# IC2.net
KiCad netlist of a schematic drawn in Altium Designer
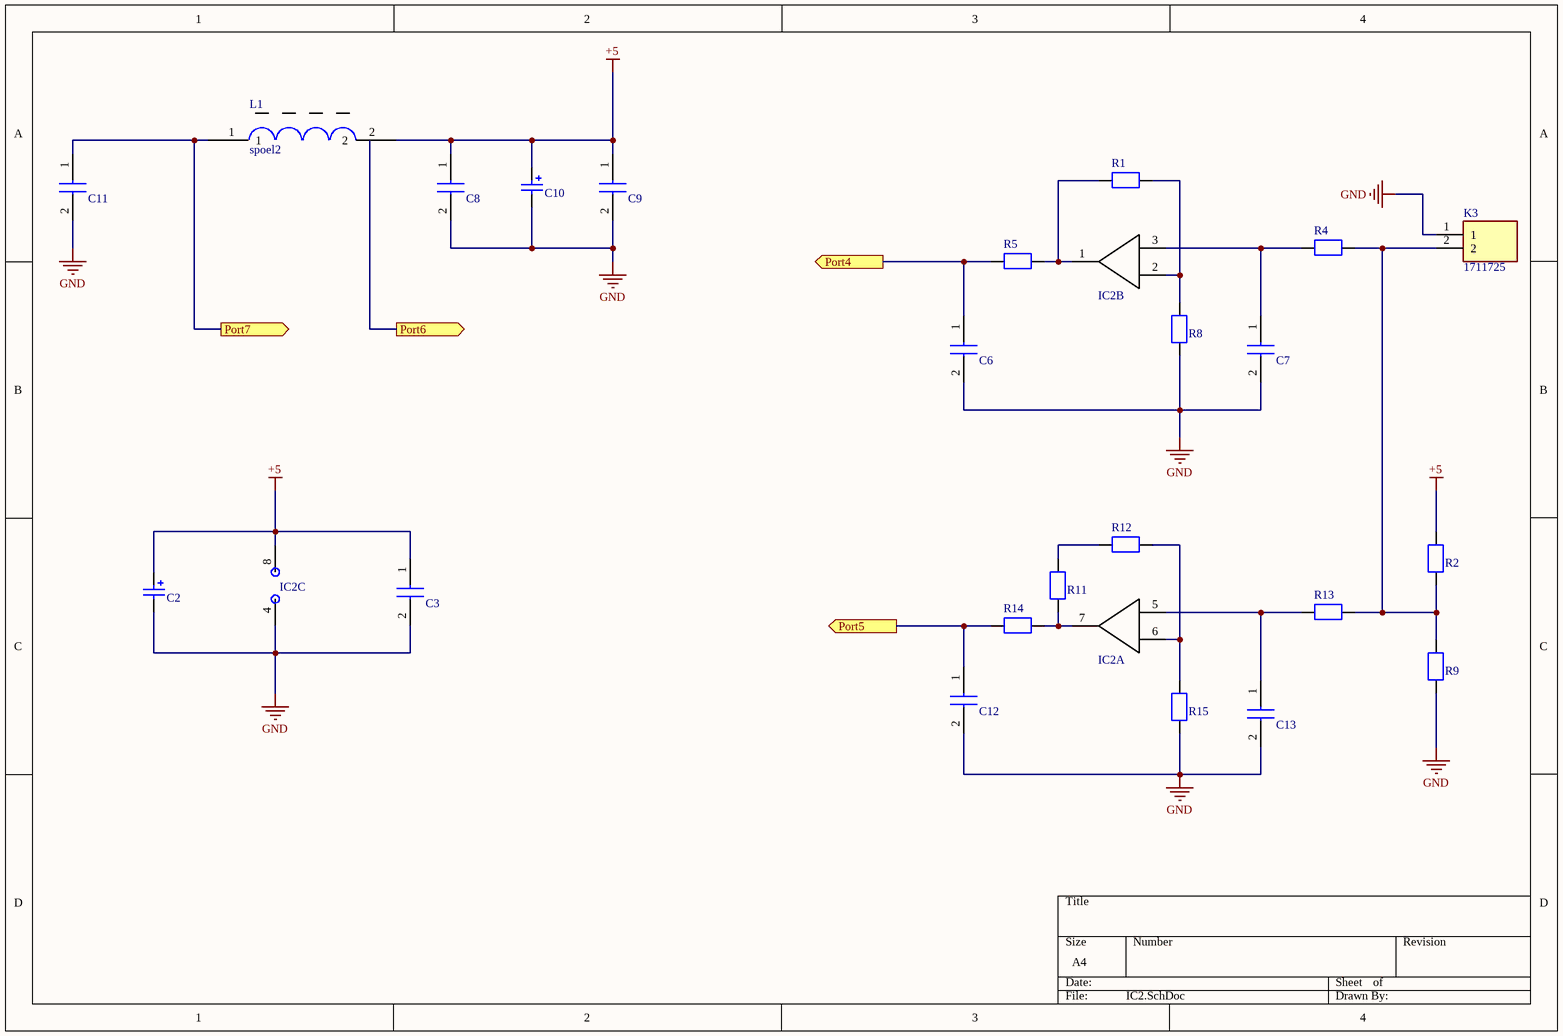
[diagram p0: IC2.SchDoc]

(export (version "E")
  (design (tool "Eeschema 10.0.6"))
  (components
    (comp (ref "C2")
      (value "10uF")
      (footprint "WCAP-ATG8_D5H11")
      (description "WCAP-ATG8 Aluminum Electrolytic Capacitor, Radial THT, D5xH11mm, 10uF, 50V")
      (fields
        (field (name "MANUFACTURER") "Wurth Elektronik")
        (field (name "MANUFACTURER PART NUMBER") "860010672009")
      )
      (libsource (lib "SoldeerboutLib") (part "860010672009"))
    )
    (comp (ref "C3")
      (value "08055A130JAT2A")
      (footprint "SamacSys:CAPC2012X94N")
      (description "Capacitor")
      (fields (field (name "MOUSER PART NUMBER") "581-08055A130JAT2A"))
      (libsource (lib "SoldeerboutLib") (part "08055A130JAT2A"))
    )
    (comp (ref "C6")
      (value "08055A130JAT2A")
      (footprint "SamacSys:CAPC2012X94N")
      (description "Capacitor")
      (fields (field (name "MOUSER PART NUMBER") "581-08055A130JAT2A"))
      (libsource (lib "SoldeerboutLib") (part "08055A130JAT2A"))
    )
    (comp (ref "C7")
      (value "08055A130JAT2A")
      (footprint "SamacSys:CAPC2012X94N")
      (description "Capacitor")
      (fields (field (name "MOUSER PART NUMBER") "581-08055A130JAT2A"))
      (libsource (lib "SoldeerboutLib") (part "08055A130JAT2A"))
    )
    (comp (ref "C8")
      (value "08055A130JAT2A")
      (footprint "SamacSys:CAPC2012X94N")
      (description "Capacitor")
      (fields (field (name "MOUSER PART NUMBER") "581-08055A130JAT2A"))
      (libsource (lib "SoldeerboutLib") (part "08055A130JAT2A"))
    )
    (comp (ref "C9")
      (value "08055A130JAT2A")
      (footprint "SamacSys:CAPC2012X94N")
      (description "Capacitor")
      (fields (field (name "MOUSER PART NUMBER") "581-08055A130JAT2A"))
      (libsource (lib "SoldeerboutLib") (part "08055A130JAT2A"))
    )
    (comp (ref "C10")
      (value "10uF")
      (footprint "WCAP-ATG8_D5H11")
      (description "WCAP-ATG8 Aluminum Electrolytic Capacitor, Radial THT, D5xH11mm, 10uF, 50V")
      (fields
        (field (name "MANUFACTURER") "Wurth Elektronik")
        (field (name "MANUFACTURER PART NUMBER") "860010672009")
      )
      (libsource (lib "SoldeerboutLib") (part "860010672009"))
    )
    (comp (ref "C11")
      (value "08055A130JAT2A")
      (footprint "SamacSys:CAPC2012X94N")
      (description "Capacitor")
      (fields (field (name "MOUSER PART NUMBER") "581-08055A130JAT2A"))
      (libsource (lib "SoldeerboutLib") (part "08055A130JAT2A"))
    )
    (comp (ref "C12")
      (value "08055A130JAT2A")
      (footprint "SamacSys:CAPC2012X94N")
      (description "Capacitor")
      (fields (field (name "MOUSER PART NUMBER") "581-08055A130JAT2A"))
      (libsource (lib "SoldeerboutLib") (part "08055A130JAT2A"))
    )
    (comp (ref "C13")
      (value "08055A130JAT2A")
      (footprint "SamacSys:CAPC2012X94N")
      (description "Capacitor")
      (fields (field (name "MOUSER PART NUMBER") "581-08055A130JAT2A"))
      (libsource (lib "SoldeerboutLib") (part "08055A130JAT2A"))
    )
    (comp (ref "IC2")
      (value "MCP6002-E_P")
      (footprint "SamacSys:DIP781W56P254L950H533Q8N")
      (description "Integrated Circuit")
      (fields
        (field (name "MANUFACTURER_PART_NUMBER") "MCP6002-E/P")
        (field (name "MOUSER PART NUMBER") "579-MCP6002-E/P")
      )
      (libsource (lib "SoldeerboutLib") (part "MCP6002-E_P"))
    )
    (comp (ref "K3")
      (value "1711725")
      (footprint "SamacSys:1711725")
      (description "Connector")
      (fields (field (name "MOUSER PART NUMBER") "651-1711725"))
      (libsource (lib "SoldeerboutLib") (part "1711725"))
    )
    (comp (ref "L1")
      (value "spoel2")
      (footprint "INDC3225X270N")
      (libsource (lib "SoldeerboutLib") (part "spoel2"))
    )
    (comp (ref "R1")
      (value "CRCW08050000Z0EA")
      (footprint "RESC2013X50X30LL20T20")
      (fields (field (name "MANUFACTURER") "Vishay Dale"))
      (libsource (lib "SoldeerboutLib") (part "resistor"))
    )
    (comp (ref "R2")
      (value "CRCW08050000Z0EA")
      (footprint "RESC2013X50X30LL20T20")
      (fields (field (name "MANUFACTURER") "Vishay Dale"))
      (libsource (lib "SoldeerboutLib") (part "resistor"))
    )
    (comp (ref "R4")
      (value "CRCW08050000Z0EA")
      (footprint "RESC2013X50X30LL20T20")
      (fields (field (name "MANUFACTURER") "Vishay Dale"))
      (libsource (lib "SoldeerboutLib") (part "resistor"))
    )
    (comp (ref "R5")
      (value "CRCW08050000Z0EA")
      (footprint "RESC2013X50X30LL20T20")
      (fields (field (name "MANUFACTURER") "Vishay Dale"))
      (libsource (lib "SoldeerboutLib") (part "resistor"))
    )
    (comp (ref "R8")
      (value "CRCW08050000Z0EA")
      (footprint "RESC2013X50X30LL20T20")
      (fields (field (name "MANUFACTURER") "Vishay Dale"))
      (libsource (lib "SoldeerboutLib") (part "resistor"))
    )
    (comp (ref "R9")
      (value "CRCW08050000Z0EA")
      (footprint "RESC2013X50X30LL20T20")
      (fields (field (name "MANUFACTURER") "Vishay Dale"))
      (libsource (lib "SoldeerboutLib") (part "resistor"))
    )
    (comp (ref "R11")
      (value "CRCW08050000Z0EA")
      (footprint "RESC2013X50X30LL20T20")
      (fields (field (name "MANUFACTURER") "Vishay Dale"))
      (libsource (lib "SoldeerboutLib") (part "resistor"))
    )
    (comp (ref "R12")
      (value "CRCW08050000Z0EA")
      (footprint "RESC2013X50X30LL20T20")
      (fields (field (name "MANUFACTURER") "Vishay Dale"))
      (libsource (lib "SoldeerboutLib") (part "resistor"))
    )
    (comp (ref "R13")
      (value "CRCW08050000Z0EA")
      (footprint "RESC2013X50X30LL20T20")
      (fields (field (name "MANUFACTURER") "Vishay Dale"))
      (libsource (lib "SoldeerboutLib") (part "resistor"))
    )
    (comp (ref "R14")
      (value "CRCW08050000Z0EA")
      (footprint "RESC2013X50X30LL20T20")
      (fields (field (name "MANUFACTURER") "Vishay Dale"))
      (libsource (lib "SoldeerboutLib") (part "resistor"))
    )
    (comp (ref "R15")
      (value "CRCW08050000Z0EA")
      (footprint "RESC2013X50X30LL20T20")
      (fields (field (name "MANUFACTURER") "Vishay Dale"))
      (libsource (lib "SoldeerboutLib") (part "resistor"))
    )
  )
  (nets
    (net (code "1") (name "+5") (class "Default")
      (node (ref "C10") (pin "1") (pinfunction "P_1") (pintype "passive"))
      (node (ref "C2") (pin "1") (pinfunction "P_1") (pintype "passive"))
      (node (ref "C3") (pin "1") (pinfunction "1_1") (pintype "passive"))
      (node (ref "C8") (pin "1") (pinfunction "1_1") (pintype "passive"))
      (node (ref "C9") (pin "1") (pinfunction "1_1") (pintype "passive"))
      (node (ref "L1") (pin "2") (pinfunction "2_2") (pintype "passive"))
      (node (ref "R2") (pin "2") (pinfunction "2_2") (pintype "passive"))
    )
    (net (code "2") (name "/Port4") (class "Default")
      (node (ref "C6") (pin "1") (pinfunction "1_1") (pintype "passive"))
      (node (ref "R5") (pin "1") (pinfunction "1_1") (pintype "passive"))
    )
    (net (code "3") (name "/Port5") (class "Default")
      (node (ref "C12") (pin "1") (pinfunction "1_1") (pintype "passive"))
      (node (ref "R14") (pin "1") (pinfunction "1_1") (pintype "passive"))
    )
    (net (code "5") (name "/Port7") (class "Default")
      (node (ref "C11") (pin "1") (pinfunction "1_1") (pintype "passive"))
      (node (ref "L1") (pin "1") (pinfunction "1_1") (pintype "passive"))
    )
    (net (code "6") (name "GND") (class "Default")
      (node (ref "C10") (pin "2") (pinfunction "N_2") (pintype "passive"))
      (node (ref "C11") (pin "2") (pinfunction "2_2") (pintype "passive"))
      (node (ref "C12") (pin "2") (pinfunction "2_2") (pintype "passive"))
      (node (ref "C13") (pin "2") (pinfunction "2_2") (pintype "passive"))
      (node (ref "C2") (pin "2") (pinfunction "N_2") (pintype "passive"))
      (node (ref "C3") (pin "2") (pinfunction "2_2") (pintype "passive"))
      (node (ref "C6") (pin "2") (pinfunction "2_2") (pintype "passive"))
      (node (ref "C7") (pin "2") (pinfunction "2_2") (pintype "passive"))
      (node (ref "C8") (pin "2") (pinfunction "2_2") (pintype "passive"))
      (node (ref "C9") (pin "2") (pinfunction "2_2") (pintype "passive"))
      (node (ref "K3") (pin "1") (pinfunction "1_1") (pintype "passive"))
      (node (ref "R15") (pin "1") (pinfunction "1_1") (pintype "passive"))
      (node (ref "R8") (pin "1") (pinfunction "1_1") (pintype "passive"))
      (node (ref "R9") (pin "1") (pinfunction "1_1") (pintype "passive"))
    )
    (net (code "7") (name "Net-(IC2A-VINB+)") (class "Default")
      (node (ref "C13") (pin "1") (pinfunction "1_1") (pintype "passive"))
      (node (ref "IC2") (pin "5") (pinfunction "VINB+_5") (pintype "passive"))
      (node (ref "R13") (pin "1") (pinfunction "1_1") (pintype "passive"))
    )
    (net (code "8") (name "Net-(IC2A-VINB-)") (class "Default")
      (node (ref "IC2") (pin "6") (pinfunction "VINB-_6") (pintype "passive"))
      (node (ref "R12") (pin "2") (pinfunction "2_2") (pintype "passive"))
      (node (ref "R15") (pin "2") (pinfunction "2_2") (pintype "passive"))
    )
    (net (code "9") (name "Net-(IC2A-VOUTB)") (class "Default")
      (node (ref "IC2") (pin "7") (pinfunction "VOUTB_7") (pintype "passive"))
      (node (ref "R11") (pin "1") (pinfunction "1_1") (pintype "passive"))
      (node (ref "R14") (pin "2") (pinfunction "2_2") (pintype "passive"))
    )
    (net (code "10") (name "Net-(IC2B-VINA+)") (class "Default")
      (node (ref "C7") (pin "1") (pinfunction "1_1") (pintype "passive"))
      (node (ref "IC2") (pin "3") (pinfunction "VINA+_3") (pintype "passive"))
      (node (ref "R4") (pin "1") (pinfunction "1_1") (pintype "passive"))
    )
    (net (code "11") (name "Net-(IC2B-VINA-)") (class "Default")
      (node (ref "IC2") (pin "2") (pinfunction "VINA-_2") (pintype "passive"))
      (node (ref "R1") (pin "2") (pinfunction "2_2") (pintype "passive"))
      (node (ref "R8") (pin "2") (pinfunction "2_2") (pintype "passive"))
    )
    (net (code "12") (name "Net-(IC2B-VOUTA)") (class "Default")
      (node (ref "IC2") (pin "1") (pinfunction "VOUTA_1") (pintype "passive"))
      (node (ref "R1") (pin "1") (pinfunction "1_1") (pintype "passive"))
      (node (ref "R5") (pin "2") (pinfunction "2_2") (pintype "passive"))
    )
    (net (code "13") (name "Net-(K3-Pad2)") (class "Default")
      (node (ref "K3") (pin "2") (pinfunction "2_2") (pintype "passive"))
      (node (ref "R13") (pin "2") (pinfunction "2_2") (pintype "passive"))
      (node (ref "R2") (pin "1") (pinfunction "1_1") (pintype "passive"))
      (node (ref "R4") (pin "2") (pinfunction "2_2") (pintype "passive"))
      (node (ref "R9") (pin "2") (pinfunction "2_2") (pintype "passive"))
    )
    (net (code "14") (name "Net-(R11-Pad2)") (class "Default")
      (node (ref "R11") (pin "2") (pinfunction "2_2") (pintype "passive"))
      (node (ref "R12") (pin "1") (pinfunction "1_1") (pintype "passive"))
    )
    (net (code "15") (name "unconnected-(IC2C-VDD-Pad8)") (class "Default")
      (node (ref "IC2") (pin "8") (pinfunction "VDD_8") (pintype "passive"))
    )
    (net (code "16") (name "unconnected-(IC2C-VSS-Pad4)") (class "Default")
      (node (ref "IC2") (pin "4") (pinfunction "VSS_4") (pintype "passive"))
    )
  )
)
